# cpld.net
KiCad netlist of a schematic drawn in EAGLE
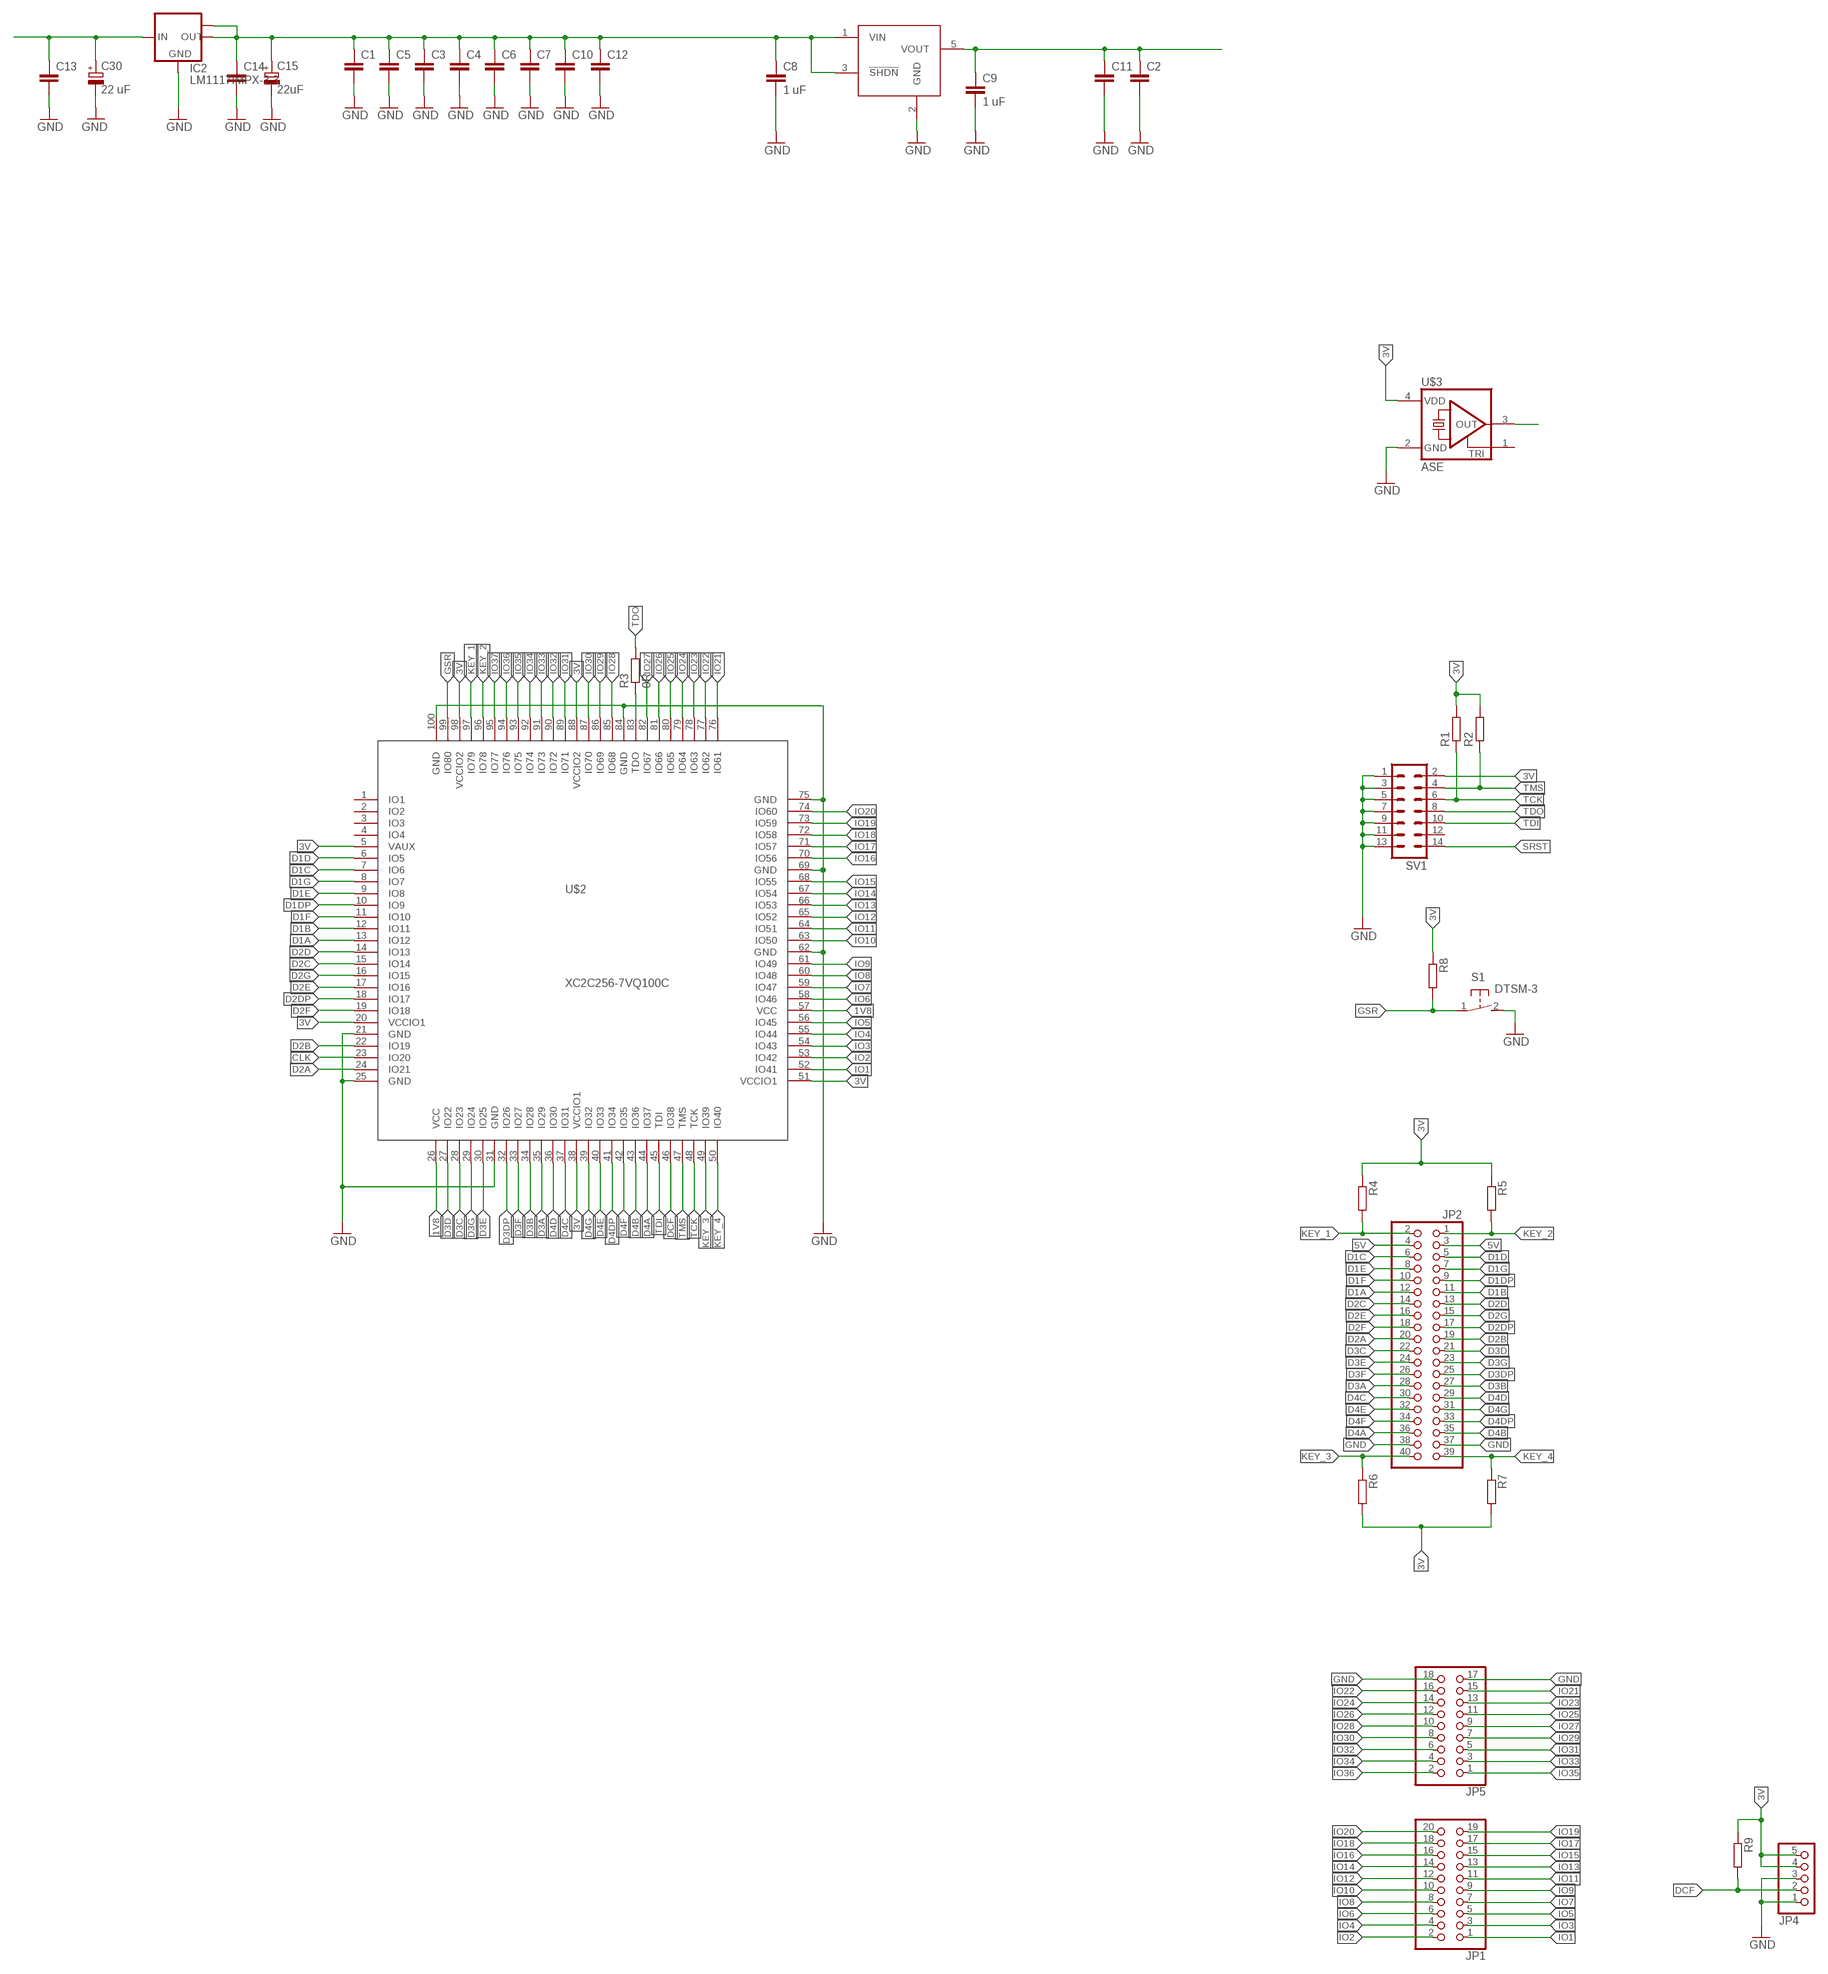
[diagram p0: schematic, sheet 1]

(export (version "E")
  (design (tool "Eeschema 10.0.6"))
  (components
    (comp (ref "C1")
      (value "C-EUC0603")
      (footprint "eagle-import:C0603")
      (libsource (lib "eagle-import") (part "C-EUC0603"))
    )
    (comp (ref "C2")
      (value "C-EUC0603")
      (footprint "eagle-import:C0603")
      (libsource (lib "eagle-import") (part "C-EUC0603"))
    )
    (comp (ref "C3")
      (value "C-EUC0402")
      (footprint "eagle-import:C0402")
      (libsource (lib "eagle-import") (part "C-EUC0402"))
    )
    (comp (ref "C4")
      (value "C-EUC0603")
      (footprint "eagle-import:C0603")
      (libsource (lib "eagle-import") (part "C-EUC0603"))
    )
    (comp (ref "C5")
      (value "C-EUC0603")
      (footprint "eagle-import:C0603")
      (libsource (lib "eagle-import") (part "C-EUC0603"))
    )
    (comp (ref "C6")
      (value "C-EUC0402")
      (footprint "eagle-import:C0402")
      (libsource (lib "eagle-import") (part "C-EUC0402"))
    )
    (comp (ref "C7")
      (value "C-EUC0603")
      (footprint "eagle-import:C0603")
      (libsource (lib "eagle-import") (part "C-EUC0603"))
    )
    (comp (ref "C8")
      (value "1 uF")
      (footprint "eagle-import:C0603")
      (libsource (lib "eagle-import") (part "C-EUC0603"))
    )
    (comp (ref "C9")
      (value "1 uF")
      (footprint "eagle-import:C0603")
      (libsource (lib "eagle-import") (part "C-EUC0603"))
    )
    (comp (ref "C10")
      (value "C-EUC0603")
      (footprint "eagle-import:C0603")
      (libsource (lib "eagle-import") (part "C-EUC0603"))
    )
    (comp (ref "C11")
      (value "C-EUC0603")
      (footprint "eagle-import:C0603")
      (libsource (lib "eagle-import") (part "C-EUC0603"))
    )
    (comp (ref "C12")
      (value "C-EUC0603")
      (footprint "eagle-import:C0603")
      (libsource (lib "eagle-import") (part "C-EUC0603"))
    )
    (comp (ref "C13")
      (value "C-EUC0603")
      (footprint "eagle-import:C0603")
      (libsource (lib "eagle-import") (part "C-EUC0603"))
    )
    (comp (ref "C14")
      (value "C-EUC0603")
      (footprint "eagle-import:C0603")
      (libsource (lib "eagle-import") (part "C-EUC0603"))
    )
    (comp (ref "C15")
      (value "22uF")
      (footprint "eagle-import:SMC_A")
      (libsource (lib "eagle-import") (part "CPOL-EUSMCA"))
    )
    (comp (ref "C30")
      (value "22 uF")
      (footprint "eagle-import:SMC_A")
      (libsource (lib "eagle-import") (part "CPOL-EUSMCA"))
    )
    (comp (ref "IC2")
      (value "LM1117IMPX-3.3")
      (footprint "eagle-import:SOT223")
      (libsource (lib "eagle-import") (part "LM1117IMPX-3.3"))
    )
    (comp (ref "JP1")
      (value "PINHD-2X10")
      (footprint "eagle-import:2X10")
      (libsource (lib "eagle-import") (part "PINHD-2X10"))
    )
    (comp (ref "JP2")
      (value "PINHD-2X20_2.54-SMD")
      (footprint "eagle-import:2X20SMD")
      (libsource (lib "eagle-import") (part "PINHD-2X20_2.54-SMD"))
    )
    (comp (ref "JP4")
      (value "PINHD-1X5")
      (footprint "eagle-import:1X05")
      (libsource (lib "eagle-import") (part "PINHD-1X5"))
    )
    (comp (ref "JP5")
      (value "PINHD-2X9")
      (footprint "eagle-import:2X09")
      (libsource (lib "eagle-import") (part "PINHD-2X9"))
    )
    (comp (ref "R1")
      (value "R-EU_R0402")
      (footprint "eagle-import:R0402")
      (libsource (lib "eagle-import") (part "R-EU_R0402"))
    )
    (comp (ref "R2")
      (value "R-EU_R0402")
      (footprint "eagle-import:R0402")
      (libsource (lib "eagle-import") (part "R-EU_R0402"))
    )
    (comp (ref "R3")
      (value "0R")
      (footprint "eagle-import:R1206")
      (libsource (lib "eagle-import") (part "R-EU_R1206"))
    )
    (comp (ref "R4")
      (value "R-EU_R0402")
      (footprint "eagle-import:R0402")
      (libsource (lib "eagle-import") (part "R-EU_R0402"))
    )
    (comp (ref "R5")
      (value "R-EU_R0603")
      (footprint "eagle-import:R0603")
      (libsource (lib "eagle-import") (part "R-EU_R0603"))
    )
    (comp (ref "R6")
      (value "R-EU_R0603")
      (footprint "eagle-import:R0603")
      (libsource (lib "eagle-import") (part "R-EU_R0603"))
    )
    (comp (ref "R7")
      (value "R-EU_R0603")
      (footprint "eagle-import:R0603")
      (libsource (lib "eagle-import") (part "R-EU_R0603"))
    )
    (comp (ref "R8")
      (value "R-EU_R0603")
      (footprint "eagle-import:R0603")
      (libsource (lib "eagle-import") (part "R-EU_R0603"))
    )
    (comp (ref "R9")
      (value "R-EU_R0603")
      (footprint "eagle-import:R0603")
      (libsource (lib "eagle-import") (part "R-EU_R0603"))
    )
    (comp (ref "S1")
      (value "DTSM-3")
      (footprint "eagle-import:DTSM-3")
      (libsource (lib "eagle-import") (part "DTSM-3"))
    )
    (comp (ref "SV1")
      (value "ML14")
      (footprint "eagle-import:ML14")
      (libsource (lib "eagle-import") (part "ML14"))
    )
    (comp (ref "U$1")
      (value "MCP1802")
      (footprint "eagle-import:SOT23-5")
      (libsource (lib "eagle-import") (part "MCP1802"))
    )
    (comp (ref "U$2")
      (value "XC2C256-7VQ100C")
      (footprint "eagle-import:TQFP100")
      (libsource (lib "eagle-import") (part "XC2C256-7VQ100C"))
    )
    (comp (ref "U$3")
      (value "ASE")
      (footprint "eagle-import:ASE")
      (libsource (lib "eagle-import") (part "ASE"))
    )
  )
  (nets
    (net (code "1") (name "1V8") (class "Default")
      (node (ref "C11") (pin "1") (pinfunction "1_1") (pintype "passive"))
      (node (ref "C2") (pin "1") (pinfunction "1_1") (pintype "passive"))
      (node (ref "C9") (pin "1") (pinfunction "1_1") (pintype "passive"))
      (node (ref "U$1") (pin "5") (pinfunction "VOUT_5") (pintype "power_in"))
      (node (ref "U$2") (pin "26") (pinfunction "VCC_26") (pintype "bidirectional"))
      (node (ref "U$2") (pin "57") (pinfunction "VCC_57") (pintype "bidirectional"))
    )
    (net (code "2") (name "3V") (class "Default")
      (node (ref "C1") (pin "1") (pinfunction "1_1") (pintype "passive"))
      (node (ref "C10") (pin "1") (pinfunction "1_1") (pintype "passive"))
      (node (ref "C12") (pin "1") (pinfunction "1_1") (pintype "passive"))
      (node (ref "C14") (pin "1") (pinfunction "1_1") (pintype "passive"))
      (node (ref "C15") (pin "+") (pinfunction "+_+") (pintype "passive"))
      (node (ref "C3") (pin "1") (pinfunction "1_1") (pintype "passive"))
      (node (ref "C4") (pin "1") (pinfunction "1_1") (pintype "passive"))
      (node (ref "C5") (pin "1") (pinfunction "1_1") (pintype "passive"))
      (node (ref "C6") (pin "1") (pinfunction "1_1") (pintype "passive"))
      (node (ref "C7") (pin "1") (pinfunction "1_1") (pintype "passive"))
      (node (ref "C8") (pin "1") (pinfunction "1_1") (pintype "passive"))
      (node (ref "IC2") (pin "2") (pinfunction "OUT_2") (pintype "passive"))
      (node (ref "IC2") (pin "TAB") (pinfunction "OUT1_TAB") (pintype "passive"))
      (node (ref "JP4") (pin "4") (pinfunction "4_4") (pintype "passive"))
      (node (ref "JP4") (pin "5") (pinfunction "5_5") (pintype "passive"))
      (node (ref "R1") (pin "2") (pinfunction "2_2") (pintype "passive"))
      (node (ref "R2") (pin "2") (pinfunction "2_2") (pintype "passive"))
      (node (ref "R4") (pin "1") (pinfunction "1_1") (pintype "passive"))
      (node (ref "R5") (pin "1") (pinfunction "1_1") (pintype "passive"))
      (node (ref "R6") (pin "2") (pinfunction "2_2") (pintype "passive"))
      (node (ref "R7") (pin "2") (pinfunction "2_2") (pintype "passive"))
      (node (ref "R8") (pin "1") (pinfunction "1_1") (pintype "passive"))
      (node (ref "R9") (pin "1") (pinfunction "1_1") (pintype "passive"))
      (node (ref "SV1") (pin "2") (pinfunction "2_2") (pintype "passive"))
      (node (ref "U$1") (pin "1") (pinfunction "VIN_1") (pintype "power_in"))
      (node (ref "U$1") (pin "3") (pinfunction "~{SHDN}_3") (pintype "input"))
      (node (ref "U$2") (pin "20") (pinfunction "VCCIO1_20") (pintype "bidirectional"))
      (node (ref "U$2") (pin "38") (pinfunction "VCCIO1_38") (pintype "bidirectional"))
      (node (ref "U$2") (pin "5") (pinfunction "VAUX_5") (pintype "bidirectional"))
      (node (ref "U$2") (pin "51") (pinfunction "VCCIO1_51") (pintype "bidirectional"))
      (node (ref "U$2") (pin "88") (pinfunction "VCCIO2_88") (pintype "bidirectional"))
      (node (ref "U$2") (pin "98") (pinfunction "VCCIO2_98") (pintype "bidirectional"))
      (node (ref "U$3") (pin "4") (pinfunction "VDD_4") (pintype "power_in"))
    )
    (net (code "3") (name "5V") (class "Default")
      (node (ref "C13") (pin "1") (pinfunction "1_1") (pintype "passive"))
      (node (ref "C30") (pin "+") (pinfunction "+_+") (pintype "passive"))
      (node (ref "IC2") (pin "3") (pinfunction "IN_3") (pintype "input"))
      (node (ref "JP2") (pin "3") (pinfunction "3_3") (pintype "passive"))
      (node (ref "JP2") (pin "4") (pinfunction "4_4") (pintype "passive"))
    )
    (net (code "4") (name "CLK") (class "Default")
      (node (ref "U$2") (pin "23") (pinfunction "IO20_23") (pintype "bidirectional"))
      (node (ref "U$3") (pin "3") (pinfunction "OUT_3") (pintype "output"))
    )
    (net (code "5") (name "D1A") (class "Default")
      (node (ref "JP2") (pin "12") (pinfunction "12_12") (pintype "passive"))
      (node (ref "U$2") (pin "13") (pinfunction "IO12_13") (pintype "bidirectional"))
    )
    (net (code "6") (name "D1B") (class "Default")
      (node (ref "JP2") (pin "11") (pinfunction "11_11") (pintype "passive"))
      (node (ref "U$2") (pin "12") (pinfunction "IO11_12") (pintype "bidirectional"))
    )
    (net (code "7") (name "D1C") (class "Default")
      (node (ref "JP2") (pin "6") (pinfunction "6_6") (pintype "passive"))
      (node (ref "U$2") (pin "7") (pinfunction "IO6_7") (pintype "bidirectional"))
    )
    (net (code "8") (name "D1D") (class "Default")
      (node (ref "JP2") (pin "5") (pinfunction "5_5") (pintype "passive"))
      (node (ref "U$2") (pin "6") (pinfunction "IO5_6") (pintype "bidirectional"))
    )
    (net (code "9") (name "D1DP") (class "Default")
      (node (ref "JP2") (pin "9") (pinfunction "9_9") (pintype "passive"))
      (node (ref "U$2") (pin "10") (pinfunction "IO9_10") (pintype "bidirectional"))
    )
    (net (code "10") (name "D1E") (class "Default")
      (node (ref "JP2") (pin "8") (pinfunction "8_8") (pintype "passive"))
      (node (ref "U$2") (pin "9") (pinfunction "IO8_9") (pintype "bidirectional"))
    )
    (net (code "11") (name "D1F") (class "Default")
      (node (ref "JP2") (pin "10") (pinfunction "10_10") (pintype "passive"))
      (node (ref "U$2") (pin "11") (pinfunction "IO10_11") (pintype "bidirectional"))
    )
    (net (code "12") (name "D1G") (class "Default")
      (node (ref "JP2") (pin "7") (pinfunction "7_7") (pintype "passive"))
      (node (ref "U$2") (pin "8") (pinfunction "IO7_8") (pintype "bidirectional"))
    )
    (net (code "13") (name "D2A") (class "Default")
      (node (ref "JP2") (pin "20") (pinfunction "20_20") (pintype "passive"))
      (node (ref "U$2") (pin "24") (pinfunction "IO21_24") (pintype "bidirectional"))
    )
    (net (code "14") (name "D2B") (class "Default")
      (node (ref "JP2") (pin "19") (pinfunction "19_19") (pintype "passive"))
      (node (ref "U$2") (pin "22") (pinfunction "IO19_22") (pintype "bidirectional"))
    )
    (net (code "15") (name "D2C") (class "Default")
      (node (ref "JP2") (pin "14") (pinfunction "14_14") (pintype "passive"))
      (node (ref "U$2") (pin "15") (pinfunction "IO14_15") (pintype "bidirectional"))
    )
    (net (code "16") (name "D2D") (class "Default")
      (node (ref "JP2") (pin "13") (pinfunction "13_13") (pintype "passive"))
      (node (ref "U$2") (pin "14") (pinfunction "IO13_14") (pintype "bidirectional"))
    )
    (net (code "17") (name "D2DP") (class "Default")
      (node (ref "JP2") (pin "17") (pinfunction "17_17") (pintype "passive"))
      (node (ref "U$2") (pin "18") (pinfunction "IO17_18") (pintype "bidirectional"))
    )
    (net (code "18") (name "D2E") (class "Default")
      (node (ref "JP2") (pin "16") (pinfunction "16_16") (pintype "passive"))
      (node (ref "U$2") (pin "17") (pinfunction "IO16_17") (pintype "bidirectional"))
    )
    (net (code "19") (name "D2F") (class "Default")
      (node (ref "JP2") (pin "18") (pinfunction "18_18") (pintype "passive"))
      (node (ref "U$2") (pin "19") (pinfunction "IO18_19") (pintype "bidirectional"))
    )
    (net (code "20") (name "D2G") (class "Default")
      (node (ref "JP2") (pin "15") (pinfunction "15_15") (pintype "passive"))
      (node (ref "U$2") (pin "16") (pinfunction "IO15_16") (pintype "bidirectional"))
    )
    (net (code "21") (name "D3A") (class "Default")
      (node (ref "JP2") (pin "28") (pinfunction "28_28") (pintype "passive"))
      (node (ref "U$2") (pin "35") (pinfunction "IO29_35") (pintype "bidirectional"))
    )
    (net (code "22") (name "D3B") (class "Default")
      (node (ref "JP2") (pin "27") (pinfunction "27_27") (pintype "passive"))
      (node (ref "U$2") (pin "34") (pinfunction "IO28_34") (pintype "bidirectional"))
    )
    (net (code "23") (name "D3C") (class "Default")
      (node (ref "JP2") (pin "22") (pinfunction "22_22") (pintype "passive"))
      (node (ref "U$2") (pin "28") (pinfunction "IO23_28") (pintype "bidirectional"))
    )
    (net (code "24") (name "D3D") (class "Default")
      (node (ref "JP2") (pin "21") (pinfunction "21_21") (pintype "passive"))
      (node (ref "U$2") (pin "27") (pinfunction "IO22_27") (pintype "bidirectional"))
    )
    (net (code "25") (name "D3DP") (class "Default")
      (node (ref "JP2") (pin "25") (pinfunction "25_25") (pintype "passive"))
      (node (ref "U$2") (pin "32") (pinfunction "IO26_32") (pintype "bidirectional"))
    )
    (net (code "26") (name "D3E") (class "Default")
      (node (ref "JP2") (pin "24") (pinfunction "24_24") (pintype "passive"))
      (node (ref "U$2") (pin "30") (pinfunction "IO25_30") (pintype "bidirectional"))
    )
    (net (code "27") (name "D3F") (class "Default")
      (node (ref "JP2") (pin "26") (pinfunction "26_26") (pintype "passive"))
      (node (ref "U$2") (pin "33") (pinfunction "IO27_33") (pintype "bidirectional"))
    )
    (net (code "28") (name "D3G") (class "Default")
      (node (ref "JP2") (pin "23") (pinfunction "23_23") (pintype "passive"))
      (node (ref "U$2") (pin "29") (pinfunction "IO24_29") (pintype "bidirectional"))
    )
    (net (code "29") (name "D4A") (class "Default")
      (node (ref "JP2") (pin "36") (pinfunction "36_36") (pintype "passive"))
      (node (ref "U$2") (pin "44") (pinfunction "IO37_44") (pintype "bidirectional"))
    )
    (net (code "30") (name "D4B") (class "Default")
      (node (ref "JP2") (pin "35") (pinfunction "35_35") (pintype "passive"))
      (node (ref "U$2") (pin "43") (pinfunction "IO36_43") (pintype "bidirectional"))
    )
    (net (code "31") (name "D4C") (class "Default")
      (node (ref "JP2") (pin "30") (pinfunction "30_30") (pintype "passive"))
      (node (ref "U$2") (pin "37") (pinfunction "IO31_37") (pintype "bidirectional"))
    )
    (net (code "32") (name "D4D") (class "Default")
      (node (ref "JP2") (pin "29") (pinfunction "29_29") (pintype "passive"))
      (node (ref "U$2") (pin "36") (pinfunction "IO30_36") (pintype "bidirectional"))
    )
    (net (code "33") (name "D4DP") (class "Default")
      (node (ref "JP2") (pin "33") (pinfunction "33_33") (pintype "passive"))
      (node (ref "U$2") (pin "41") (pinfunction "IO34_41") (pintype "bidirectional"))
    )
    (net (code "34") (name "D4E") (class "Default")
      (node (ref "JP2") (pin "32") (pinfunction "32_32") (pintype "passive"))
      (node (ref "U$2") (pin "40") (pinfunction "IO33_40") (pintype "bidirectional"))
    )
    (net (code "35") (name "D4F") (class "Default")
      (node (ref "JP2") (pin "34") (pinfunction "34_34") (pintype "passive"))
      (node (ref "U$2") (pin "42") (pinfunction "IO35_42") (pintype "bidirectional"))
    )
    (net (code "36") (name "D4G") (class "Default")
      (node (ref "JP2") (pin "31") (pinfunction "31_31") (pintype "passive"))
      (node (ref "U$2") (pin "39") (pinfunction "IO32_39") (pintype "bidirectional"))
    )
    (net (code "37") (name "DCF") (class "Default")
      (node (ref "JP4") (pin "2") (pinfunction "2_2") (pintype "passive"))
      (node (ref "R9") (pin "2") (pinfunction "2_2") (pintype "passive"))
      (node (ref "U$2") (pin "46") (pinfunction "IO38_46") (pintype "bidirectional"))
    )
    (net (code "38") (name "GND") (class "Default")
      (node (ref "C1") (pin "2") (pinfunction "2_2") (pintype "passive"))
      (node (ref "C10") (pin "2") (pinfunction "2_2") (pintype "passive"))
      (node (ref "C11") (pin "2") (pinfunction "2_2") (pintype "passive"))
      (node (ref "C12") (pin "2") (pinfunction "2_2") (pintype "passive"))
      (node (ref "C13") (pin "2") (pinfunction "2_2") (pintype "passive"))
      (node (ref "C14") (pin "2") (pinfunction "2_2") (pintype "passive"))
      (node (ref "C15") (pin "-") (pinfunction "-_-") (pintype "passive"))
      (node (ref "C2") (pin "2") (pinfunction "2_2") (pintype "passive"))
      (node (ref "C3") (pin "2") (pinfunction "2_2") (pintype "passive"))
      (node (ref "C30") (pin "-") (pinfunction "-_-") (pintype "passive"))
      (node (ref "C4") (pin "2") (pinfunction "2_2") (pintype "passive"))
      (node (ref "C5") (pin "2") (pinfunction "2_2") (pintype "passive"))
      (node (ref "C6") (pin "2") (pinfunction "2_2") (pintype "passive"))
      (node (ref "C7") (pin "2") (pinfunction "2_2") (pintype "passive"))
      (node (ref "C8") (pin "2") (pinfunction "2_2") (pintype "passive"))
      (node (ref "C9") (pin "2") (pinfunction "2_2") (pintype "passive"))
      (node (ref "IC2") (pin "1") (pinfunction "GND_1") (pintype "input"))
      (node (ref "JP2") (pin "37") (pinfunction "37_37") (pintype "passive"))
      (node (ref "JP2") (pin "38") (pinfunction "38_38") (pintype "passive"))
      (node (ref "JP4") (pin "1") (pinfunction "1_1") (pintype "passive"))
      (node (ref "JP4") (pin "3") (pinfunction "3_3") (pintype "passive"))
      (node (ref "JP5") (pin "17") (pinfunction "17_17") (pintype "passive"))
      (node (ref "JP5") (pin "18") (pinfunction "18_18") (pintype "passive"))
      (node (ref "S1") (pin "2") (pinfunction "2_2") (pintype "passive"))
      (node (ref "SV1") (pin "1") (pinfunction "1_1") (pintype "passive"))
      (node (ref "SV1") (pin "11") (pinfunction "11_11") (pintype "passive"))
      (node (ref "SV1") (pin "13") (pinfunction "13_13") (pintype "passive"))
      (node (ref "SV1") (pin "3") (pinfunction "3_3") (pintype "passive"))
      (node (ref "SV1") (pin "5") (pinfunction "5_5") (pintype "passive"))
      (node (ref "SV1") (pin "7") (pinfunction "7_7") (pintype "passive"))
      (node (ref "SV1") (pin "9") (pinfunction "9_9") (pintype "passive"))
      (node (ref "U$1") (pin "2") (pinfunction "GND_2") (pintype "power_in"))
      (node (ref "U$2") (pin "100") (pinfunction "GND_100") (pintype "bidirectional"))
      (node (ref "U$2") (pin "21") (pinfunction "GND_21") (pintype "bidirectional"))
      (node (ref "U$2") (pin "25") (pinfunction "GND_25") (pintype "bidirectional"))
      (node (ref "U$2") (pin "31") (pinfunction "GND_31") (pintype "bidirectional"))
      (node (ref "U$2") (pin "62") (pinfunction "GND_62") (pintype "bidirectional"))
      (node (ref "U$2") (pin "69") (pinfunction "GND_69") (pintype "bidirectional"))
      (node (ref "U$2") (pin "75") (pinfunction "GND_75") (pintype "bidirectional"))
      (node (ref "U$2") (pin "84") (pinfunction "GND_84") (pintype "bidirectional"))
      (node (ref "U$3") (pin "2") (pinfunction "GND_2") (pintype "power_in"))
    )
    (net (code "39") (name "GSR") (class "Default")
      (node (ref "R8") (pin "2") (pinfunction "2_2") (pintype "passive"))
      (node (ref "S1") (pin "1") (pinfunction "1_1") (pintype "passive"))
      (node (ref "U$2") (pin "99") (pinfunction "IO80_99") (pintype "bidirectional"))
    )
    (net (code "40") (name "IO1") (class "Default")
      (node (ref "JP1") (pin "1") (pinfunction "1_1") (pintype "passive"))
      (node (ref "U$2") (pin "52") (pinfunction "IO41_52") (pintype "bidirectional"))
    )
    (net (code "41") (name "IO2") (class "Default")
      (node (ref "JP1") (pin "2") (pinfunction "2_2") (pintype "passive"))
      (node (ref "U$2") (pin "53") (pinfunction "IO42_53") (pintype "bidirectional"))
    )
    (net (code "42") (name "IO3") (class "Default")
      (node (ref "JP1") (pin "3") (pinfunction "3_3") (pintype "passive"))
      (node (ref "U$2") (pin "54") (pinfunction "IO43_54") (pintype "bidirectional"))
    )
    (net (code "43") (name "IO4") (class "Default")
      (node (ref "JP1") (pin "4") (pinfunction "4_4") (pintype "passive"))
      (node (ref "U$2") (pin "55") (pinfunction "IO44_55") (pintype "bidirectional"))
    )
    (net (code "44") (name "IO5") (class "Default")
      (node (ref "JP1") (pin "5") (pinfunction "5_5") (pintype "passive"))
      (node (ref "U$2") (pin "56") (pinfunction "IO45_56") (pintype "bidirectional"))
    )
    (net (code "45") (name "IO6") (class "Default")
      (node (ref "JP1") (pin "6") (pinfunction "6_6") (pintype "passive"))
      (node (ref "U$2") (pin "58") (pinfunction "IO46_58") (pintype "bidirectional"))
    )
    (net (code "46") (name "IO7") (class "Default")
      (node (ref "JP1") (pin "7") (pinfunction "7_7") (pintype "passive"))
      (node (ref "U$2") (pin "59") (pinfunction "IO47_59") (pintype "bidirectional"))
    )
    (net (code "47") (name "IO8") (class "Default")
      (node (ref "JP1") (pin "8") (pinfunction "8_8") (pintype "passive"))
      (node (ref "U$2") (pin "60") (pinfunction "IO48_60") (pintype "bidirectional"))
    )
    (net (code "48") (name "IO9") (class "Default")
      (node (ref "JP1") (pin "9") (pinfunction "9_9") (pintype "passive"))
      (node (ref "U$2") (pin "61") (pinfunction "IO49_61") (pintype "bidirectional"))
    )
    (net (code "49") (name "IO10") (class "Default")
      (node (ref "JP1") (pin "10") (pinfunction "10_10") (pintype "passive"))
      (node (ref "U$2") (pin "63") (pinfunction "IO50_63") (pintype "bidirectional"))
    )
    (net (code "50") (name "IO11") (class "Default")
      (node (ref "JP1") (pin "11") (pinfunction "11_11") (pintype "passive"))
      (node (ref "U$2") (pin "64") (pinfunction "IO51_64") (pintype "bidirectional"))
    )
    (net (code "51") (name "IO12") (class "Default")
      (node (ref "JP1") (pin "12") (pinfunction "12_12") (pintype "passive"))
      (node (ref "U$2") (pin "65") (pinfunction "IO52_65") (pintype "bidirectional"))
    )
    (net (code "52") (name "IO13") (class "Default")
      (node (ref "JP1") (pin "13") (pinfunction "13_13") (pintype "passive"))
      (node (ref "U$2") (pin "66") (pinfunction "IO53_66") (pintype "bidirectional"))
    )
    (net (code "53") (name "IO14") (class "Default")
      (node (ref "JP1") (pin "14") (pinfunction "14_14") (pintype "passive"))
      (node (ref "U$2") (pin "67") (pinfunction "IO54_67") (pintype "bidirectional"))
    )
    (net (code "54") (name "IO15") (class "Default")
      (node (ref "JP1") (pin "15") (pinfunction "15_15") (pintype "passive"))
      (node (ref "U$2") (pin "68") (pinfunction "IO55_68") (pintype "bidirectional"))
    )
    (net (code "55") (name "IO16") (class "Default")
      (node (ref "JP1") (pin "16") (pinfunction "16_16") (pintype "passive"))
      (node (ref "U$2") (pin "70") (pinfunction "IO56_70") (pintype "bidirectional"))
    )
    (net (code "56") (name "IO17") (class "Default")
      (node (ref "JP1") (pin "17") (pinfunction "17_17") (pintype "passive"))
      (node (ref "U$2") (pin "71") (pinfunction "IO57_71") (pintype "bidirectional"))
    )
    (net (code "57") (name "IO18") (class "Default")
      (node (ref "JP1") (pin "18") (pinfunction "18_18") (pintype "passive"))
      (node (ref "U$2") (pin "72") (pinfunction "IO58_72") (pintype "bidirectional"))
    )
    (net (code "58") (name "IO19") (class "Default")
      (node (ref "JP1") (pin "19") (pinfunction "19_19") (pintype "passive"))
      (node (ref "U$2") (pin "73") (pinfunction "IO59_73") (pintype "bidirectional"))
    )
    (net (code "59") (name "IO20") (class "Default")
      (node (ref "JP1") (pin "20") (pinfunction "20_20") (pintype "passive"))
      (node (ref "U$2") (pin "74") (pinfunction "IO60_74") (pintype "bidirectional"))
    )
    (net (code "60") (name "IO21") (class "Default")
      (node (ref "JP5") (pin "15") (pinfunction "15_15") (pintype "passive"))
      (node (ref "U$2") (pin "76") (pinfunction "IO61_76") (pintype "bidirectional"))
    )
    (net (code "61") (name "IO22") (class "Default")
      (node (ref "JP5") (pin "16") (pinfunction "16_16") (pintype "passive"))
      (node (ref "U$2") (pin "77") (pinfunction "IO62_77") (pintype "bidirectional"))
    )
    (net (code "62") (name "IO23") (class "Default")
      (node (ref "JP5") (pin "13") (pinfunction "13_13") (pintype "passive"))
      (node (ref "U$2") (pin "78") (pinfunction "IO63_78") (pintype "bidirectional"))
    )
    (net (code "63") (name "IO24") (class "Default")
      (node (ref "JP5") (pin "14") (pinfunction "14_14") (pintype "passive"))
      (node (ref "U$2") (pin "79") (pinfunction "IO64_79") (pintype "bidirectional"))
    )
    (net (code "64") (name "IO25") (class "Default")
      (node (ref "JP5") (pin "11") (pinfunction "11_11") (pintype "passive"))
      (node (ref "U$2") (pin "80") (pinfunction "IO65_80") (pintype "bidirectional"))
    )
    (net (code "65") (name "IO26") (class "Default")
      (node (ref "JP5") (pin "12") (pinfunction "12_12") (pintype "passive"))
      (node (ref "U$2") (pin "81") (pinfunction "IO66_81") (pintype "bidirectional"))
    )
    (net (code "66") (name "IO27") (class "Default")
      (node (ref "JP5") (pin "9") (pinfunction "9_9") (pintype "passive"))
      (node (ref "U$2") (pin "82") (pinfunction "IO67_82") (pintype "bidirectional"))
    )
    (net (code "67") (name "IO28") (class "Default")
      (node (ref "JP5") (pin "10") (pinfunction "10_10") (pintype "passive"))
      (node (ref "U$2") (pin "85") (pinfunction "IO68_85") (pintype "bidirectional"))
    )
    (net (code "68") (name "IO29") (class "Default")
      (node (ref "JP5") (pin "7") (pinfunction "7_7") (pintype "passive"))
      (node (ref "U$2") (pin "86") (pinfunction "IO69_86") (pintype "bidirectional"))
    )
    (net (code "69") (name "IO30") (class "Default")
      (node (ref "JP5") (pin "8") (pinfunction "8_8") (pintype "passive"))
      (node (ref "U$2") (pin "87") (pinfunction "IO70_87") (pintype "bidirectional"))
    )
    (net (code "70") (name "IO31") (class "Default")
      (node (ref "JP5") (pin "5") (pinfunction "5_5") (pintype "passive"))
      (node (ref "U$2") (pin "89") (pinfunction "IO71_89") (pintype "bidirectional"))
    )
    (net (code "71") (name "IO32") (class "Default")
      (node (ref "JP5") (pin "6") (pinfunction "6_6") (pintype "passive"))
      (node (ref "U$2") (pin "90") (pinfunction "IO72_90") (pintype "bidirectional"))
    )
    (net (code "72") (name "IO33") (class "Default")
      (node (ref "JP5") (pin "3") (pinfunction "3_3") (pintype "passive"))
      (node (ref "U$2") (pin "91") (pinfunction "IO73_91") (pintype "bidirectional"))
    )
    (net (code "73") (name "IO34") (class "Default")
      (node (ref "JP5") (pin "4") (pinfunction "4_4") (pintype "passive"))
      (node (ref "U$2") (pin "92") (pinfunction "IO74_92") (pintype "bidirectional"))
    )
    (net (code "74") (name "IO35") (class "Default")
      (node (ref "JP5") (pin "1") (pinfunction "1_1") (pintype "passive"))
      (node (ref "U$2") (pin "93") (pinfunction "IO75_93") (pintype "bidirectional"))
    )
    (net (code "75") (name "IO36") (class "Default")
      (node (ref "JP5") (pin "2") (pinfunction "2_2") (pintype "passive"))
      (node (ref "U$2") (pin "94") (pinfunction "IO76_94") (pintype "bidirectional"))
    )
    (net (code "76") (name "IO37") (class "Default")
      (node (ref "U$2") (pin "95") (pinfunction "IO77_95") (pintype "bidirectional"))
    )
    (net (code "77") (name "KEY_1") (class "Default")
      (node (ref "JP2") (pin "2") (pinfunction "2_2") (pintype "passive"))
      (node (ref "R4") (pin "2") (pinfunction "2_2") (pintype "passive"))
      (node (ref "U$2") (pin "97") (pinfunction "IO79_97") (pintype "bidirectional"))
    )
    (net (code "78") (name "KEY_2") (class "Default")
      (node (ref "JP2") (pin "1") (pinfunction "1_1") (pintype "passive"))
      (node (ref "R5") (pin "2") (pinfunction "2_2") (pintype "passive"))
      (node (ref "U$2") (pin "96") (pinfunction "IO78_96") (pintype "bidirectional"))
    )
    (net (code "79") (name "KEY_3") (class "Default")
      (node (ref "JP2") (pin "40") (pinfunction "40_40") (pintype "passive"))
      (node (ref "R6") (pin "1") (pinfunction "1_1") (pintype "passive"))
      (node (ref "U$2") (pin "49") (pinfunction "IO39_49") (pintype "bidirectional"))
    )
    (net (code "80") (name "KEY_4") (class "Default")
      (node (ref "JP2") (pin "39") (pinfunction "39_39") (pintype "passive"))
      (node (ref "R7") (pin "1") (pinfunction "1_1") (pintype "passive"))
      (node (ref "U$2") (pin "50") (pinfunction "IO40_50") (pintype "bidirectional"))
    )
    (net (code "81") (name "Net-(U$2-TDO)") (class "Default")
      (node (ref "R3") (pin "1") (pinfunction "1_1") (pintype "passive"))
      (node (ref "U$2") (pin "83") (pinfunction "TDO_83") (pintype "bidirectional"))
    )
    (net (code "82") (name "SRST") (class "Default")
      (node (ref "SV1") (pin "14") (pinfunction "14_14") (pintype "passive"))
    )
    (net (code "83") (name "TCK") (class "Default")
      (node (ref "R1") (pin "1") (pinfunction "1_1") (pintype "passive"))
      (node (ref "SV1") (pin "6") (pinfunction "6_6") (pintype "passive"))
      (node (ref "U$2") (pin "48") (pinfunction "TCK_48") (pintype "bidirectional"))
    )
    (net (code "84") (name "TDI") (class "Default")
      (node (ref "SV1") (pin "10") (pinfunction "10_10") (pintype "passive"))
      (node (ref "U$2") (pin "45") (pinfunction "TDI_45") (pintype "bidirectional"))
    )
    (net (code "85") (name "TDO") (class "Default")
      (node (ref "R3") (pin "2") (pinfunction "2_2") (pintype "passive"))
      (node (ref "SV1") (pin "8") (pinfunction "8_8") (pintype "passive"))
    )
    (net (code "86") (name "TMS") (class "Default")
      (node (ref "R2") (pin "1") (pinfunction "1_1") (pintype "passive"))
      (node (ref "SV1") (pin "4") (pinfunction "4_4") (pintype "passive"))
      (node (ref "U$2") (pin "47") (pinfunction "TMS_47") (pintype "bidirectional"))
    )
    (net (code "87") (name "unconnected-(SV1-Pad12)") (class "Default")
      (node (ref "SV1") (pin "12") (pinfunction "12_12") (pintype "passive"))
    )
    (net (code "88") (name "unconnected-(U$2-IO1-Pad1)") (class "Default")
      (node (ref "U$2") (pin "1") (pinfunction "IO1_1") (pintype "bidirectional"))
    )
    (net (code "89") (name "unconnected-(U$2-IO2-Pad2)") (class "Default")
      (node (ref "U$2") (pin "2") (pinfunction "IO2_2") (pintype "bidirectional"))
    )
    (net (code "90") (name "unconnected-(U$2-IO3-Pad3)") (class "Default")
      (node (ref "U$2") (pin "3") (pinfunction "IO3_3") (pintype "bidirectional"))
    )
    (net (code "91") (name "unconnected-(U$2-IO4-Pad4)") (class "Default")
      (node (ref "U$2") (pin "4") (pinfunction "IO4_4") (pintype "bidirectional"))
    )
    (net (code "92") (name "unconnected-(U$3-TRI-Pad1)") (class "Default")
      (node (ref "U$3") (pin "1") (pinfunction "TRI_1") (pintype "input"))
    )
  )
)
